# tick-wifi-mk-1_1.net
KiCad netlist of a schematic drawn in EAGLE
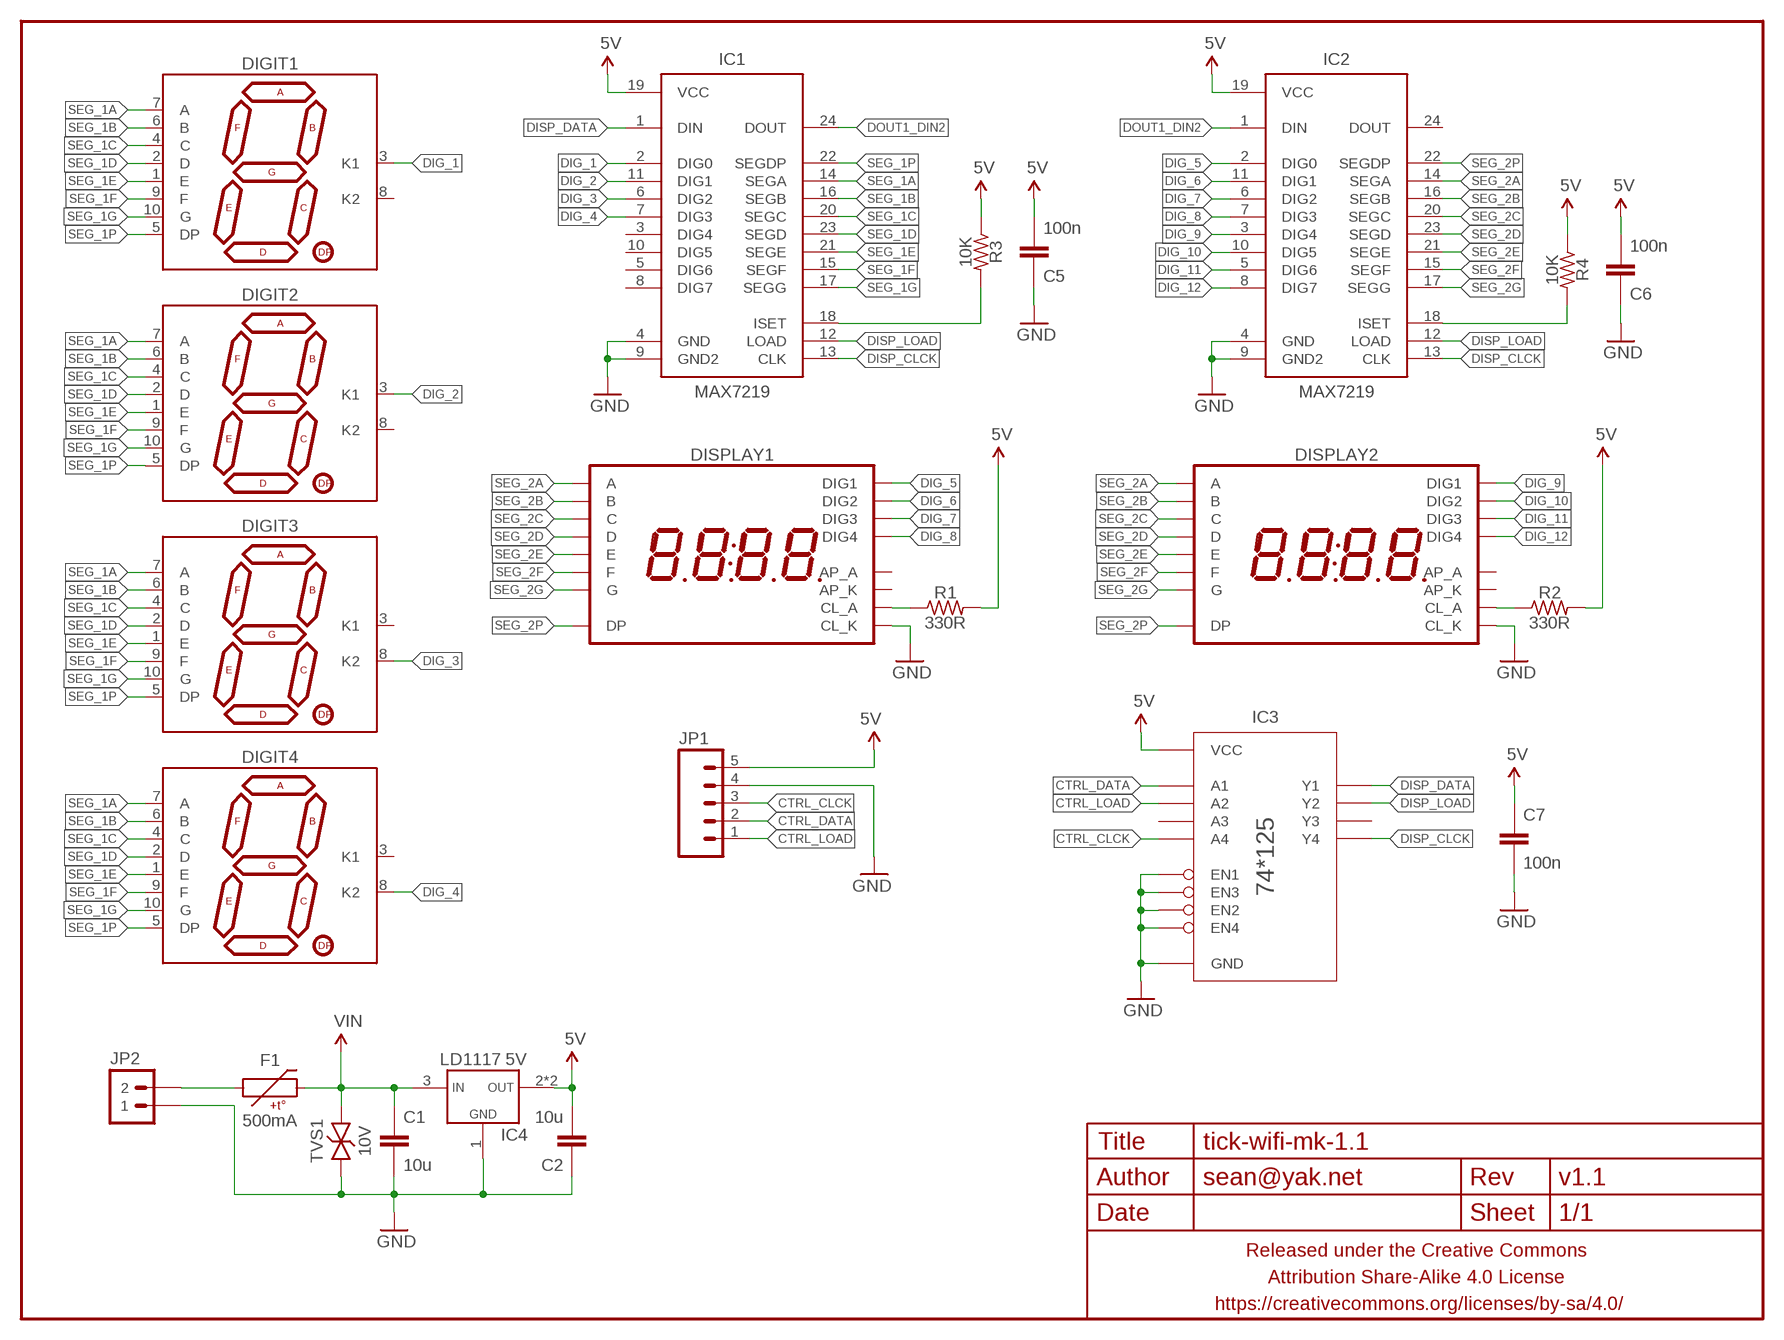
[diagram p0: schematic, sheet 1]

(export (version "E")
  (design (tool "Eeschema 10.0.6"))
  (components
    (comp (ref "C1")
      (value "10u")
      (footprint "eagle-import:C1210")
      (libsource (lib "eagle-import") (part "CAPACITOR-CERAMICC1210"))
    )
    (comp (ref "C2")
      (value "10u")
      (footprint "eagle-import:C1210")
      (libsource (lib "eagle-import") (part "CAPACITOR-CERAMICC1210"))
    )
    (comp (ref "C5")
      (value "100n")
      (footprint "eagle-import:C0603")
      (libsource (lib "eagle-import") (part "CAPACITOR-CERAMICC0603"))
    )
    (comp (ref "C6")
      (value "100n")
      (footprint "eagle-import:C0603")
      (libsource (lib "eagle-import") (part "CAPACITOR-CERAMICC0603"))
    )
    (comp (ref "C7")
      (value "100n")
      (footprint "eagle-import:C0603")
      (libsource (lib "eagle-import") (part "CAPACITOR-CERAMICC0603"))
    )
    (comp (ref "DIGIT1")
      (value "7SEG_1DIGPTH-25.4MM-BARE")
      (footprint "eagle-import:7SEG_1DIG_25.4MM_NOSILK")
      (libsource (lib "eagle-import") (part "7SEG_1DIGPTH-25.4MM-BARE"))
    )
    (comp (ref "DIGIT2")
      (value "7SEG_1DIGPTH-25.4MM-BARE")
      (footprint "eagle-import:7SEG_1DIG_25.4MM_NOSILK")
      (libsource (lib "eagle-import") (part "7SEG_1DIGPTH-25.4MM-BARE"))
    )
    (comp (ref "DIGIT3")
      (value "7SEG_1DIGPTH-25.4MM-BARE")
      (footprint "eagle-import:7SEG_1DIG_25.4MM_NOSILK")
      (libsource (lib "eagle-import") (part "7SEG_1DIGPTH-25.4MM-BARE"))
    )
    (comp (ref "DIGIT4")
      (value "7SEG_1DIGPTH-25.4MM-BARE")
      (footprint "eagle-import:7SEG_1DIG_25.4MM_NOSILK")
      (libsource (lib "eagle-import") (part "7SEG_1DIGPTH-25.4MM-BARE"))
    )
    (comp (ref "DISPLAY1")
      (value "7SEG_4DIGIT_COLON_APOS")
      (footprint "eagle-import:7SEG_4DIG_10MM")
      (libsource (lib "eagle-import") (part "7SEG_4DIGIT_COLON_APOS"))
    )
    (comp (ref "DISPLAY2")
      (value "7SEG_4DIGIT_COLON_APOS")
      (footprint "eagle-import:7SEG_4DIG_10MM")
      (libsource (lib "eagle-import") (part "7SEG_4DIGIT_COLON_APOS"))
    )
    (comp (ref "F1")
      (value "500mA")
      (footprint "eagle-import:PTC-1210")
      (libsource (lib "eagle-import") (part "PTCPTC-1210"))
    )
    (comp (ref "FRAME1")
      (value "FRAME-LETTERNO_PACKAGE")
      (footprint "eagle-import:DUMMY")
      (fields (field (name "DESIGNER") "sean@yak.net") (field (name "VERSION") "v1.1"))
      (libsource (lib "eagle-import") (part "FRAME-LETTERNO_PACKAGE"))
    )
    (comp (ref "IC1")
      (value "MAX7219")
      (footprint "eagle-import:SO24W")
      (libsource (lib "eagle-import") (part "MAX7219SOIC-W"))
    )
    (comp (ref "IC2")
      (value "MAX7219")
      (footprint "eagle-import:SO24W")
      (libsource (lib "eagle-import") (part "MAX7219SOIC-W"))
    )
    (comp (ref "IC3")
      (value "74HC125")
      (footprint "eagle-import:SO14")
      (libsource (lib "eagle-import") (part "74125SOIC14"))
    )
    (comp (ref "IC4")
      (value "LD1117 5V")
      (footprint "eagle-import:SOT223")
      (libsource (lib "eagle-import") (part "VREG_1117SOT223"))
    )
    (comp (ref "JP1")
      (value "M05PTH-CENTERED")
      (footprint "eagle-import:1X05_PTH_CENTERED")
      (libsource (lib "eagle-import") (part "M05PTH-CENTERED"))
    )
    (comp (ref "JP2")
      (value "M02PTH-CENTERED-R+")
      (footprint "eagle-import:1X02-CENTER-R+")
      (libsource (lib "eagle-import") (part "M02PTH-CENTERED-R+"))
    )
    (comp (ref "R1")
      (value "330R")
      (footprint "eagle-import:R0603")
      (libsource (lib "eagle-import") (part "RESISTORR0603"))
    )
    (comp (ref "R2")
      (value "330R")
      (footprint "eagle-import:R0603")
      (libsource (lib "eagle-import") (part "RESISTORR0603"))
    )
    (comp (ref "R3")
      (value "10K")
      (footprint "eagle-import:R0603")
      (libsource (lib "eagle-import") (part "RESISTORR0603"))
    )
    (comp (ref "R4")
      (value "10K")
      (footprint "eagle-import:R0603")
      (libsource (lib "eagle-import") (part "RESISTORR0603"))
    )
    (comp (ref "TVS1")
      (value "10V")
      (footprint "eagle-import:SMA-DIODE-TVS-BIDIR")
      (libsource (lib "eagle-import") (part "TVSSMA"))
    )
  )
  (nets
    (net (code "1") (name "5V") (class "Default")
      (node (ref "C2") (pin "2") (pinfunction "2_2") (pintype "passive"))
      (node (ref "C5") (pin "2") (pinfunction "2_2") (pintype "passive"))
      (node (ref "C6") (pin "2") (pinfunction "2_2") (pintype "passive"))
      (node (ref "C7") (pin "1") (pinfunction "1_1") (pintype "passive"))
      (node (ref "IC1") (pin "19") (pinfunction "VCC_19") (pintype "bidirectional"))
      (node (ref "IC2") (pin "19") (pinfunction "VCC_19") (pintype "bidirectional"))
      (node (ref "IC3") (pin "14") (pinfunction "VCC_14") (pintype "bidirectional"))
      (node (ref "IC4") (pin "2") (pinfunction "VOUT_2") (pintype "bidirectional"))
      (node (ref "IC4") (pin "4") (pinfunction "VOUT_4") (pintype "bidirectional"))
      (node (ref "JP1") (pin "5") (pinfunction "5_5") (pintype "passive"))
      (node (ref "R1") (pin "2") (pinfunction "2_2") (pintype "passive"))
      (node (ref "R2") (pin "2") (pinfunction "2_2") (pintype "passive"))
      (node (ref "R3") (pin "1") (pinfunction "1_1") (pintype "passive"))
      (node (ref "R4") (pin "1") (pinfunction "1_1") (pintype "passive"))
    )
    (net (code "2") (name "CTRL_CLCK") (class "Default")
      (node (ref "IC3") (pin "12") (pinfunction "A4_12") (pintype "bidirectional"))
      (node (ref "JP1") (pin "3") (pinfunction "3_3") (pintype "passive"))
    )
    (net (code "3") (name "CTRL_DATA") (class "Default")
      (node (ref "IC3") (pin "2") (pinfunction "A1_2") (pintype "bidirectional"))
      (node (ref "JP1") (pin "2") (pinfunction "2_2") (pintype "passive"))
    )
    (net (code "4") (name "CTRL_LOAD") (class "Default")
      (node (ref "IC3") (pin "5") (pinfunction "A2_5") (pintype "bidirectional"))
      (node (ref "JP1") (pin "1") (pinfunction "1_1") (pintype "passive"))
    )
    (net (code "5") (name "DIG_1") (class "Default")
      (node (ref "DIGIT1") (pin "3") (pinfunction "K1_3") (pintype "bidirectional"))
      (node (ref "IC1") (pin "2") (pinfunction "DIG0_2") (pintype "bidirectional"))
    )
    (net (code "6") (name "DIG_2") (class "Default")
      (node (ref "DIGIT2") (pin "3") (pinfunction "K1_3") (pintype "bidirectional"))
      (node (ref "IC1") (pin "11") (pinfunction "DIG1_11") (pintype "bidirectional"))
    )
    (net (code "7") (name "DIG_3") (class "Default")
      (node (ref "DIGIT3") (pin "8") (pinfunction "K2_8") (pintype "bidirectional"))
      (node (ref "IC1") (pin "6") (pinfunction "DIG2_6") (pintype "bidirectional"))
    )
    (net (code "8") (name "DIG_4") (class "Default")
      (node (ref "DIGIT4") (pin "8") (pinfunction "K2_8") (pintype "bidirectional"))
      (node (ref "IC1") (pin "7") (pinfunction "DIG3_7") (pintype "bidirectional"))
    )
    (net (code "9") (name "DIG_5") (class "Default")
      (node (ref "DISPLAY1") (pin "1") (pinfunction "DIG1_1") (pintype "passive"))
      (node (ref "IC2") (pin "2") (pinfunction "DIG0_2") (pintype "bidirectional"))
    )
    (net (code "10") (name "DIG_6") (class "Default")
      (node (ref "DISPLAY1") (pin "2") (pinfunction "DIG2_2") (pintype "passive"))
      (node (ref "IC2") (pin "11") (pinfunction "DIG1_11") (pintype "bidirectional"))
    )
    (net (code "11") (name "DIG_7") (class "Default")
      (node (ref "DISPLAY1") (pin "6") (pinfunction "DIG3_6") (pintype "passive"))
      (node (ref "IC2") (pin "6") (pinfunction "DIG2_6") (pintype "bidirectional"))
    )
    (net (code "12") (name "DIG_8") (class "Default")
      (node (ref "DISPLAY1") (pin "8") (pinfunction "DIG4_8") (pintype "passive"))
      (node (ref "IC2") (pin "7") (pinfunction "DIG3_7") (pintype "bidirectional"))
    )
    (net (code "13") (name "DIG_9") (class "Default")
      (node (ref "DISPLAY2") (pin "1") (pinfunction "DIG1_1") (pintype "passive"))
      (node (ref "IC2") (pin "3") (pinfunction "DIG4_3") (pintype "bidirectional"))
    )
    (net (code "14") (name "DIG_10") (class "Default")
      (node (ref "DISPLAY2") (pin "2") (pinfunction "DIG2_2") (pintype "passive"))
      (node (ref "IC2") (pin "10") (pinfunction "DIG5_10") (pintype "bidirectional"))
    )
    (net (code "15") (name "DIG_11") (class "Default")
      (node (ref "DISPLAY2") (pin "6") (pinfunction "DIG3_6") (pintype "passive"))
      (node (ref "IC2") (pin "5") (pinfunction "DIG6_5") (pintype "bidirectional"))
    )
    (net (code "16") (name "DIG_12") (class "Default")
      (node (ref "DISPLAY2") (pin "8") (pinfunction "DIG4_8") (pintype "passive"))
      (node (ref "IC2") (pin "8") (pinfunction "DIG7_8") (pintype "bidirectional"))
    )
    (net (code "17") (name "DISP_CLCK") (class "Default")
      (node (ref "IC1") (pin "13") (pinfunction "CLK_13") (pintype "bidirectional"))
      (node (ref "IC2") (pin "13") (pinfunction "CLK_13") (pintype "bidirectional"))
      (node (ref "IC3") (pin "11") (pinfunction "Y4_11") (pintype "bidirectional"))
    )
    (net (code "18") (name "DISP_DATA") (class "Default")
      (node (ref "IC1") (pin "1") (pinfunction "DIN_1") (pintype "bidirectional"))
      (node (ref "IC3") (pin "3") (pinfunction "Y1_3") (pintype "bidirectional"))
    )
    (net (code "19") (name "DISP_LOAD") (class "Default")
      (node (ref "IC1") (pin "12") (pinfunction "LOAD_12") (pintype "bidirectional"))
      (node (ref "IC2") (pin "12") (pinfunction "LOAD_12") (pintype "bidirectional"))
      (node (ref "IC3") (pin "6") (pinfunction "Y2_6") (pintype "bidirectional"))
    )
    (net (code "20") (name "DOUT1_DIN2") (class "Default")
      (node (ref "IC1") (pin "24") (pinfunction "DOUT_24") (pintype "bidirectional"))
      (node (ref "IC2") (pin "1") (pinfunction "DIN_1") (pintype "bidirectional"))
    )
    (net (code "21") (name "GND") (class "Default")
      (node (ref "C1") (pin "2") (pinfunction "2_2") (pintype "passive"))
      (node (ref "C2") (pin "1") (pinfunction "1_1") (pintype "passive"))
      (node (ref "C5") (pin "1") (pinfunction "1_1") (pintype "passive"))
      (node (ref "C6") (pin "1") (pinfunction "1_1") (pintype "passive"))
      (node (ref "C7") (pin "2") (pinfunction "2_2") (pintype "passive"))
      (node (ref "DISPLAY1") (pin "12") (pinfunction "CL_K_12") (pintype "passive"))
      (node (ref "DISPLAY2") (pin "12") (pinfunction "CL_K_12") (pintype "passive"))
      (node (ref "IC1") (pin "4") (pinfunction "GND_4") (pintype "bidirectional"))
      (node (ref "IC1") (pin "9") (pinfunction "GND2_9") (pintype "bidirectional"))
      (node (ref "IC2") (pin "4") (pinfunction "GND_4") (pintype "bidirectional"))
      (node (ref "IC2") (pin "9") (pinfunction "GND2_9") (pintype "bidirectional"))
      (node (ref "IC3") (pin "1") (pinfunction "EN1_1") (pintype "bidirectional"))
      (node (ref "IC3") (pin "10") (pinfunction "EN3_10") (pintype "bidirectional"))
      (node (ref "IC3") (pin "13") (pinfunction "EN4_13") (pintype "bidirectional"))
      (node (ref "IC3") (pin "4") (pinfunction "EN2_4") (pintype "bidirectional"))
      (node (ref "IC3") (pin "7") (pinfunction "GND_7") (pintype "bidirectional"))
      (node (ref "IC4") (pin "1") (pinfunction "GND_1") (pintype "bidirectional"))
      (node (ref "JP1") (pin "4") (pinfunction "4_4") (pintype "passive"))
      (node (ref "JP2") (pin "1") (pinfunction "1_1") (pintype "passive"))
      (node (ref "TVS1") (pin "1") (pinfunction "1_1") (pintype "passive"))
    )
    (net (code "22") (name "Net-(DISPLAY1-CL_A)") (class "Default")
      (node (ref "DISPLAY1") (pin "4") (pinfunction "CL_A_4") (pintype "passive"))
      (node (ref "R1") (pin "1") (pinfunction "1_1") (pintype "passive"))
    )
    (net (code "23") (name "Net-(DISPLAY2-CL_A)") (class "Default")
      (node (ref "DISPLAY2") (pin "4") (pinfunction "CL_A_4") (pintype "passive"))
      (node (ref "R2") (pin "1") (pinfunction "1_1") (pintype "passive"))
    )
    (net (code "24") (name "Net-(F1-Pad1)") (class "Default")
      (node (ref "F1") (pin "1") (pinfunction "1_1") (pintype "passive"))
      (node (ref "JP2") (pin "2") (pinfunction "2_2") (pintype "passive"))
    )
    (net (code "25") (name "Net-(IC1-ISET)") (class "Default")
      (node (ref "IC1") (pin "18") (pinfunction "ISET_18") (pintype "bidirectional"))
      (node (ref "R3") (pin "2") (pinfunction "2_2") (pintype "passive"))
    )
    (net (code "26") (name "Net-(IC2-ISET)") (class "Default")
      (node (ref "IC2") (pin "18") (pinfunction "ISET_18") (pintype "bidirectional"))
      (node (ref "R4") (pin "2") (pinfunction "2_2") (pintype "passive"))
    )
    (net (code "27") (name "SEG_1A") (class "Default")
      (node (ref "DIGIT1") (pin "7") (pinfunction "A_7") (pintype "bidirectional"))
      (node (ref "DIGIT2") (pin "7") (pinfunction "A_7") (pintype "bidirectional"))
      (node (ref "DIGIT3") (pin "7") (pinfunction "A_7") (pintype "bidirectional"))
      (node (ref "DIGIT4") (pin "7") (pinfunction "A_7") (pintype "bidirectional"))
      (node (ref "IC1") (pin "14") (pinfunction "SEGA_14") (pintype "bidirectional"))
    )
    (net (code "28") (name "SEG_1B") (class "Default")
      (node (ref "DIGIT1") (pin "6") (pinfunction "B_6") (pintype "bidirectional"))
      (node (ref "DIGIT2") (pin "6") (pinfunction "B_6") (pintype "bidirectional"))
      (node (ref "DIGIT3") (pin "6") (pinfunction "B_6") (pintype "bidirectional"))
      (node (ref "DIGIT4") (pin "6") (pinfunction "B_6") (pintype "bidirectional"))
      (node (ref "IC1") (pin "16") (pinfunction "SEGB_16") (pintype "bidirectional"))
    )
    (net (code "29") (name "SEG_1C") (class "Default")
      (node (ref "DIGIT1") (pin "4") (pinfunction "C_4") (pintype "bidirectional"))
      (node (ref "DIGIT2") (pin "4") (pinfunction "C_4") (pintype "bidirectional"))
      (node (ref "DIGIT3") (pin "4") (pinfunction "C_4") (pintype "bidirectional"))
      (node (ref "DIGIT4") (pin "4") (pinfunction "C_4") (pintype "bidirectional"))
      (node (ref "IC1") (pin "20") (pinfunction "SEGC_20") (pintype "bidirectional"))
    )
    (net (code "30") (name "SEG_1D") (class "Default")
      (node (ref "DIGIT1") (pin "2") (pinfunction "D_2") (pintype "bidirectional"))
      (node (ref "DIGIT2") (pin "2") (pinfunction "D_2") (pintype "bidirectional"))
      (node (ref "DIGIT3") (pin "2") (pinfunction "D_2") (pintype "bidirectional"))
      (node (ref "DIGIT4") (pin "2") (pinfunction "D_2") (pintype "bidirectional"))
      (node (ref "IC1") (pin "23") (pinfunction "SEGD_23") (pintype "bidirectional"))
    )
    (net (code "31") (name "SEG_1E") (class "Default")
      (node (ref "DIGIT1") (pin "1") (pinfunction "E_1") (pintype "bidirectional"))
      (node (ref "DIGIT2") (pin "1") (pinfunction "E_1") (pintype "bidirectional"))
      (node (ref "DIGIT3") (pin "1") (pinfunction "E_1") (pintype "bidirectional"))
      (node (ref "DIGIT4") (pin "1") (pinfunction "E_1") (pintype "bidirectional"))
      (node (ref "IC1") (pin "21") (pinfunction "SEGE_21") (pintype "bidirectional"))
    )
    (net (code "32") (name "SEG_1F") (class "Default")
      (node (ref "DIGIT1") (pin "9") (pinfunction "F_9") (pintype "bidirectional"))
      (node (ref "DIGIT2") (pin "9") (pinfunction "F_9") (pintype "bidirectional"))
      (node (ref "DIGIT3") (pin "9") (pinfunction "F_9") (pintype "bidirectional"))
      (node (ref "DIGIT4") (pin "9") (pinfunction "F_9") (pintype "bidirectional"))
      (node (ref "IC1") (pin "15") (pinfunction "SEGF_15") (pintype "bidirectional"))
    )
    (net (code "33") (name "SEG_1G") (class "Default")
      (node (ref "DIGIT1") (pin "10") (pinfunction "G_10") (pintype "bidirectional"))
      (node (ref "DIGIT2") (pin "10") (pinfunction "G_10") (pintype "bidirectional"))
      (node (ref "DIGIT3") (pin "10") (pinfunction "G_10") (pintype "bidirectional"))
      (node (ref "DIGIT4") (pin "10") (pinfunction "G_10") (pintype "bidirectional"))
      (node (ref "IC1") (pin "17") (pinfunction "SEGG_17") (pintype "bidirectional"))
    )
    (net (code "34") (name "SEG_1P") (class "Default")
      (node (ref "DIGIT1") (pin "5") (pinfunction "DP_5") (pintype "bidirectional"))
      (node (ref "DIGIT2") (pin "5") (pinfunction "DP_5") (pintype "bidirectional"))
      (node (ref "DIGIT3") (pin "5") (pinfunction "DP_5") (pintype "bidirectional"))
      (node (ref "DIGIT4") (pin "5") (pinfunction "DP_5") (pintype "bidirectional"))
      (node (ref "IC1") (pin "22") (pinfunction "SEGDP_22") (pintype "bidirectional"))
    )
    (net (code "35") (name "SEG_2A") (class "Default")
      (node (ref "DISPLAY1") (pin "14") (pinfunction "A_14") (pintype "passive"))
      (node (ref "DISPLAY2") (pin "14") (pinfunction "A_14") (pintype "passive"))
      (node (ref "IC2") (pin "14") (pinfunction "SEGA_14") (pintype "bidirectional"))
    )
    (net (code "36") (name "SEG_2B") (class "Default")
      (node (ref "DISPLAY1") (pin "16") (pinfunction "B_16") (pintype "passive"))
      (node (ref "DISPLAY2") (pin "16") (pinfunction "B_16") (pintype "passive"))
      (node (ref "IC2") (pin "16") (pinfunction "SEGB_16") (pintype "bidirectional"))
    )
    (net (code "37") (name "SEG_2C") (class "Default")
      (node (ref "DISPLAY1") (pin "13") (pinfunction "C_13") (pintype "passive"))
      (node (ref "DISPLAY2") (pin "13") (pinfunction "C_13") (pintype "passive"))
      (node (ref "IC2") (pin "20") (pinfunction "SEGC_20") (pintype "bidirectional"))
    )
    (net (code "38") (name "SEG_2D") (class "Default")
      (node (ref "DISPLAY1") (pin "3") (pinfunction "D_3") (pintype "passive"))
      (node (ref "DISPLAY2") (pin "3") (pinfunction "D_3") (pintype "passive"))
      (node (ref "IC2") (pin "23") (pinfunction "SEGD_23") (pintype "bidirectional"))
    )
    (net (code "39") (name "SEG_2E") (class "Default")
      (node (ref "DISPLAY1") (pin "5") (pinfunction "E_5") (pintype "passive"))
      (node (ref "DISPLAY2") (pin "5") (pinfunction "E_5") (pintype "passive"))
      (node (ref "IC2") (pin "21") (pinfunction "SEGE_21") (pintype "bidirectional"))
    )
    (net (code "40") (name "SEG_2F") (class "Default")
      (node (ref "DISPLAY1") (pin "11") (pinfunction "F_11") (pintype "passive"))
      (node (ref "DISPLAY2") (pin "11") (pinfunction "F_11") (pintype "passive"))
      (node (ref "IC2") (pin "15") (pinfunction "SEGF_15") (pintype "bidirectional"))
    )
    (net (code "41") (name "SEG_2G") (class "Default")
      (node (ref "DISPLAY1") (pin "15") (pinfunction "G_15") (pintype "passive"))
      (node (ref "DISPLAY2") (pin "15") (pinfunction "G_15") (pintype "passive"))
      (node (ref "IC2") (pin "17") (pinfunction "SEGG_17") (pintype "bidirectional"))
    )
    (net (code "42") (name "SEG_2P") (class "Default")
      (node (ref "DISPLAY1") (pin "7") (pinfunction "DP_7") (pintype "passive"))
      (node (ref "DISPLAY2") (pin "7") (pinfunction "DP_7") (pintype "passive"))
      (node (ref "IC2") (pin "22") (pinfunction "SEGDP_22") (pintype "bidirectional"))
    )
    (net (code "43") (name "VIN") (class "Default")
      (node (ref "C1") (pin "1") (pinfunction "1_1") (pintype "passive"))
      (node (ref "F1") (pin "2") (pinfunction "2_2") (pintype "passive"))
      (node (ref "IC4") (pin "3") (pinfunction "VIN_3") (pintype "bidirectional"))
      (node (ref "TVS1") (pin "2") (pinfunction "2_2") (pintype "passive"))
    )
    (net (code "44") (name "unconnected-(DIGIT1-K2-Pad8)") (class "Default")
      (node (ref "DIGIT1") (pin "8") (pinfunction "K2_8") (pintype "bidirectional"))
    )
    (net (code "45") (name "unconnected-(DIGIT2-K2-Pad8)") (class "Default")
      (node (ref "DIGIT2") (pin "8") (pinfunction "K2_8") (pintype "bidirectional"))
    )
    (net (code "46") (name "unconnected-(DIGIT3-K1-Pad3)") (class "Default")
      (node (ref "DIGIT3") (pin "3") (pinfunction "K1_3") (pintype "bidirectional"))
    )
    (net (code "47") (name "unconnected-(DIGIT4-K1-Pad3)") (class "Default")
      (node (ref "DIGIT4") (pin "3") (pinfunction "K1_3") (pintype "bidirectional"))
    )
    (net (code "48") (name "unconnected-(DISPLAY1-AP_A-Pad10)") (class "Default")
      (node (ref "DISPLAY1") (pin "10") (pinfunction "AP_A_10") (pintype "bidirectional"))
    )
    (net (code "49") (name "unconnected-(DISPLAY1-AP_K-Pad9)") (class "Default")
      (node (ref "DISPLAY1") (pin "9") (pinfunction "AP_K_9") (pintype "bidirectional"))
    )
    (net (code "50") (name "unconnected-(DISPLAY2-AP_A-Pad10)") (class "Default")
      (node (ref "DISPLAY2") (pin "10") (pinfunction "AP_A_10") (pintype "bidirectional"))
    )
    (net (code "51") (name "unconnected-(DISPLAY2-AP_K-Pad9)") (class "Default")
      (node (ref "DISPLAY2") (pin "9") (pinfunction "AP_K_9") (pintype "bidirectional"))
    )
    (net (code "52") (name "unconnected-(IC1-DIG4-Pad3)") (class "Default")
      (node (ref "IC1") (pin "3") (pinfunction "DIG4_3") (pintype "bidirectional"))
    )
    (net (code "53") (name "unconnected-(IC1-DIG5-Pad10)") (class "Default")
      (node (ref "IC1") (pin "10") (pinfunction "DIG5_10") (pintype "bidirectional"))
    )
    (net (code "54") (name "unconnected-(IC1-DIG6-Pad5)") (class "Default")
      (node (ref "IC1") (pin "5") (pinfunction "DIG6_5") (pintype "bidirectional"))
    )
    (net (code "55") (name "unconnected-(IC1-DIG7-Pad8)") (class "Default")
      (node (ref "IC1") (pin "8") (pinfunction "DIG7_8") (pintype "bidirectional"))
    )
    (net (code "56") (name "unconnected-(IC2-DOUT-Pad24)") (class "Default")
      (node (ref "IC2") (pin "24") (pinfunction "DOUT_24") (pintype "bidirectional"))
    )
    (net (code "57") (name "unconnected-(IC3-A3-Pad9)") (class "Default")
      (node (ref "IC3") (pin "9") (pinfunction "A3_9") (pintype "bidirectional"))
    )
    (net (code "58") (name "unconnected-(IC3-Y3-Pad8)") (class "Default")
      (node (ref "IC3") (pin "8") (pinfunction "Y3_8") (pintype "bidirectional"))
    )
  )
)
